# Convertisseur_BusCAN_vers_serial_TTL_TNN.net
KiCad netlist of a schematic drawn in EAGLE
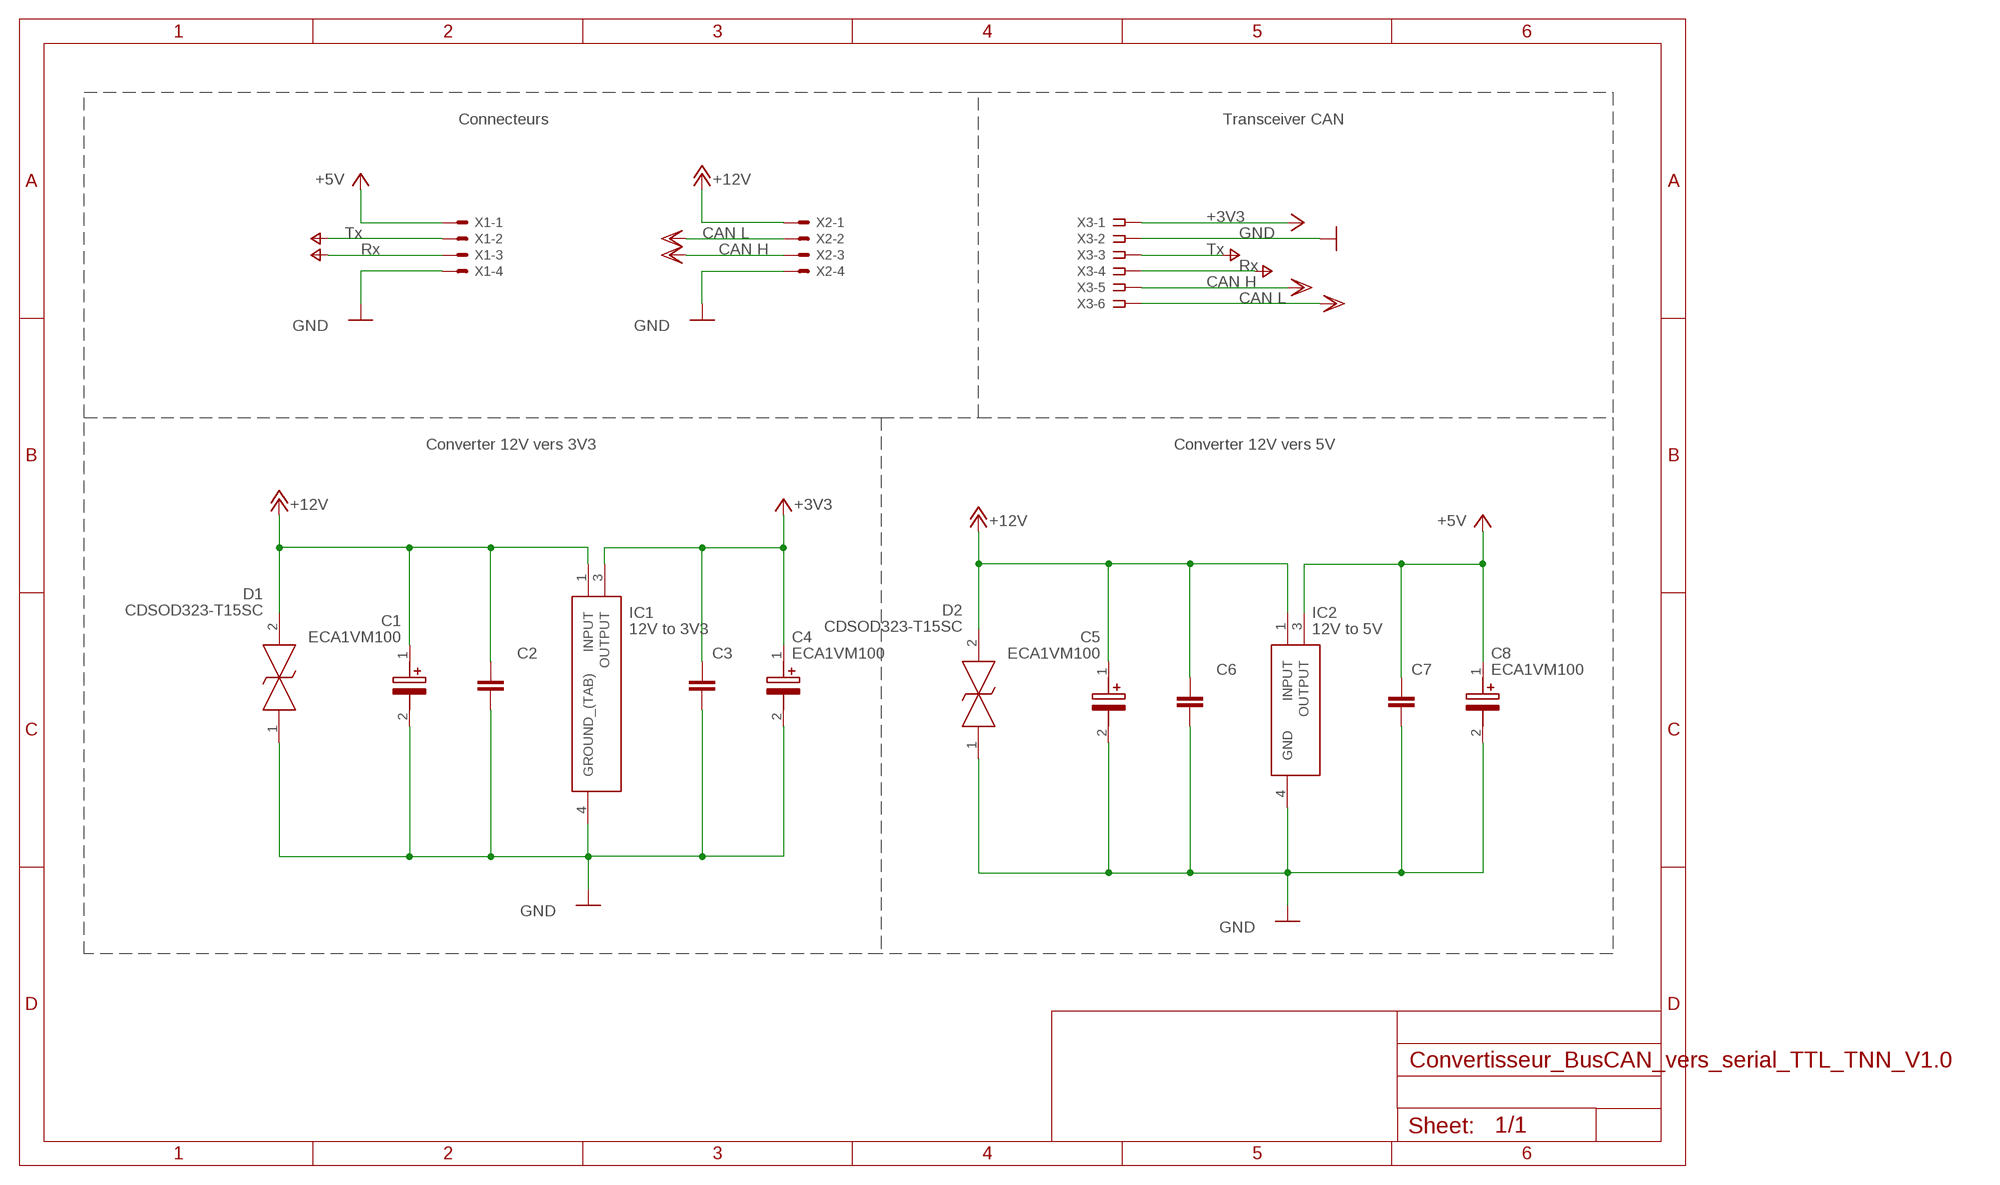
[diagram p0: schematic, sheet 1]

(export (version "E")
  (design (tool "Eeschema 10.0.6"))
  (components
    (comp (ref "C1")
      (value "ECA1VM100")
      (footprint "eagle-import:CAPPRD200W55D525H1200")
      (libsource (lib "eagle-import") (part "ECA1VM100"))
    )
    (comp (ref "C2")
      (value "C-EUC0603")
      (footprint "eagle-import:C0603")
      (libsource (lib "eagle-import") (part "C-EUC0603"))
    )
    (comp (ref "C3")
      (value "C-EUC0603")
      (footprint "eagle-import:C0603")
      (libsource (lib "eagle-import") (part "C-EUC0603"))
    )
    (comp (ref "C4")
      (value "ECA1VM100")
      (footprint "eagle-import:CAPPRD200W55D525H1200")
      (libsource (lib "eagle-import") (part "ECA1VM100"))
    )
    (comp (ref "C5")
      (value "ECA1VM100")
      (footprint "eagle-import:CAPPRD200W55D525H1200")
      (libsource (lib "eagle-import") (part "ECA1VM100"))
    )
    (comp (ref "C6")
      (value "C-EUC0603")
      (footprint "eagle-import:C0603")
      (libsource (lib "eagle-import") (part "C-EUC0603"))
    )
    (comp (ref "C7")
      (value "C-EUC0603")
      (footprint "eagle-import:C0603")
      (libsource (lib "eagle-import") (part "C-EUC0603"))
    )
    (comp (ref "C8")
      (value "ECA1VM100")
      (footprint "eagle-import:CAPPRD200W55D525H1200")
      (libsource (lib "eagle-import") (part "ECA1VM100"))
    )
    (comp (ref "D1")
      (value "CDSOD323-T15SC")
      (footprint "eagle-import:SOD-323")
      (fields (field (name "MOUSER_PART_NUMBER") "652-CDSOD323-T15SC"))
      (libsource (lib "eagle-import") (part "CDSOD323-T15SC"))
    )
    (comp (ref "D2")
      (value "CDSOD323-T15SC")
      (footprint "eagle-import:SOD-323")
      (fields (field (name "MOUSER_PART_NUMBER") "652-CDSOD323-T15SC"))
      (libsource (lib "eagle-import") (part "CDSOD323-T15SC"))
    )
    (comp (ref "IC1")
      (value "12V to 3V3")
      (footprint "eagle-import:TO228P972X240-3N")
      (fields
        (field (name "ARROW_PART_NUMBER") "LF33ABDT-TR")
        (field (name "MOUSER_PART_NUMBER") "511-LF33ABDT-TR")
      )
      (libsource (lib "eagle-import") (part "LF33ABDT-TR"))
    )
    (comp (ref "IC2")
      (value "12V to 5V")
      (footprint "eagle-import:TO228P972X240-3N")
      (fields
        (field (name "ARROW_PART_NUMBER") "L4941BDT-TR")
        (field (name "MOUSER_PART_NUMBER") "511-L4941BDT-TR")
      )
      (libsource (lib "eagle-import") (part "L4941BDT-TR"))
    )
    (comp (ref "X1")
      (value "KK-156-4")
      (footprint "eagle-import:KK-156-4")
      (fields (field (name "MF") "MOLEX"))
      (libsource (lib "eagle-import") (part "KK-156-4"))
    )
    (comp (ref "X2")
      (value "KK-156-4")
      (footprint "eagle-import:KK-156-4")
      (fields (field (name "MF") "MOLEX"))
      (libsource (lib "eagle-import") (part "KK-156-4"))
    )
    (comp (ref "X3")
      (value "SSW-106-02-G-S")
      (footprint "eagle-import:SSW-106-02-G-S")
      (fields (field (name "MF") "Samtec Inc."))
      (libsource (lib "eagle-import") (part "SSW-106-02-G-S"))
    )
  )
  (nets
    (net (code "1") (name "+3V3") (class "Default")
      (node (ref "C3") (pin "1") (pinfunction "1_1") (pintype "passive"))
      (node (ref "C4") (pin "1") (pinfunction "+_1") (pintype "bidirectional"))
      (node (ref "IC1") (pin "3") (pinfunction "OUTPUT_3") (pintype "output"))
      (node (ref "X3") (pin "1") (pinfunction "1_1") (pintype "passive"))
    )
    (net (code "2") (name "+5V") (class "Default")
      (node (ref "C7") (pin "1") (pinfunction "1_1") (pintype "passive"))
      (node (ref "C8") (pin "1") (pinfunction "+_1") (pintype "bidirectional"))
      (node (ref "IC2") (pin "3") (pinfunction "OUTPUT_3") (pintype "power_in"))
      (node (ref "X1") (pin "1") (pinfunction "S_1") (pintype "passive"))
    )
    (net (code "3") (name "+12V") (class "Default")
      (node (ref "C1") (pin "1") (pinfunction "+_1") (pintype "bidirectional"))
      (node (ref "C2") (pin "1") (pinfunction "1_1") (pintype "passive"))
      (node (ref "C5") (pin "1") (pinfunction "+_1") (pintype "bidirectional"))
      (node (ref "C6") (pin "1") (pinfunction "1_1") (pintype "passive"))
      (node (ref "D1") (pin "2") (pinfunction "2_2") (pintype "bidirectional"))
      (node (ref "D2") (pin "2") (pinfunction "2_2") (pintype "bidirectional"))
      (node (ref "IC1") (pin "1") (pinfunction "INPUT_1") (pintype "input"))
      (node (ref "IC2") (pin "1") (pinfunction "INPUT_1") (pintype "output"))
      (node (ref "X2") (pin "1") (pinfunction "S_1") (pintype "passive"))
    )
    (net (code "4") (name "CAN H") (class "Default")
      (node (ref "X2") (pin "3") (pinfunction "S_3") (pintype "passive"))
      (node (ref "X3") (pin "5") (pinfunction "1_5") (pintype "passive"))
    )
    (net (code "5") (name "CAN L") (class "Default")
      (node (ref "X2") (pin "2") (pinfunction "S_2") (pintype "passive"))
      (node (ref "X3") (pin "6") (pinfunction "1_6") (pintype "passive"))
    )
    (net (code "6") (name "GND") (class "Default")
      (node (ref "C1") (pin "2") (pinfunction "-_2") (pintype "bidirectional"))
      (node (ref "C2") (pin "2") (pinfunction "2_2") (pintype "passive"))
      (node (ref "C3") (pin "2") (pinfunction "2_2") (pintype "passive"))
      (node (ref "C4") (pin "2") (pinfunction "-_2") (pintype "bidirectional"))
      (node (ref "C5") (pin "2") (pinfunction "-_2") (pintype "bidirectional"))
      (node (ref "C6") (pin "2") (pinfunction "2_2") (pintype "passive"))
      (node (ref "C7") (pin "2") (pinfunction "2_2") (pintype "passive"))
      (node (ref "C8") (pin "2") (pinfunction "-_2") (pintype "bidirectional"))
      (node (ref "D1") (pin "1") (pinfunction "1_1") (pintype "bidirectional"))
      (node (ref "D2") (pin "1") (pinfunction "1_1") (pintype "bidirectional"))
      (node (ref "IC1") (pin "4") (pinfunction "GROUND_(TAB)_4") (pintype "bidirectional"))
      (node (ref "IC2") (pin "4") (pinfunction "GND_4") (pintype "input"))
      (node (ref "X1") (pin "4") (pinfunction "S_4") (pintype "passive"))
      (node (ref "X2") (pin "4") (pinfunction "S_4") (pintype "passive"))
      (node (ref "X3") (pin "2") (pinfunction "1_2") (pintype "passive"))
    )
    (net (code "7") (name "Rx") (class "Default")
      (node (ref "X1") (pin "3") (pinfunction "S_3") (pintype "passive"))
      (node (ref "X3") (pin "4") (pinfunction "1_4") (pintype "passive"))
    )
    (net (code "8") (name "Tx") (class "Default")
      (node (ref "X1") (pin "2") (pinfunction "S_2") (pintype "passive"))
      (node (ref "X3") (pin "3") (pinfunction "1_3") (pintype "passive"))
    )
  )
)
